# Qwiic_MP3_Trigger.net
KiCad netlist of a schematic drawn in EAGLE
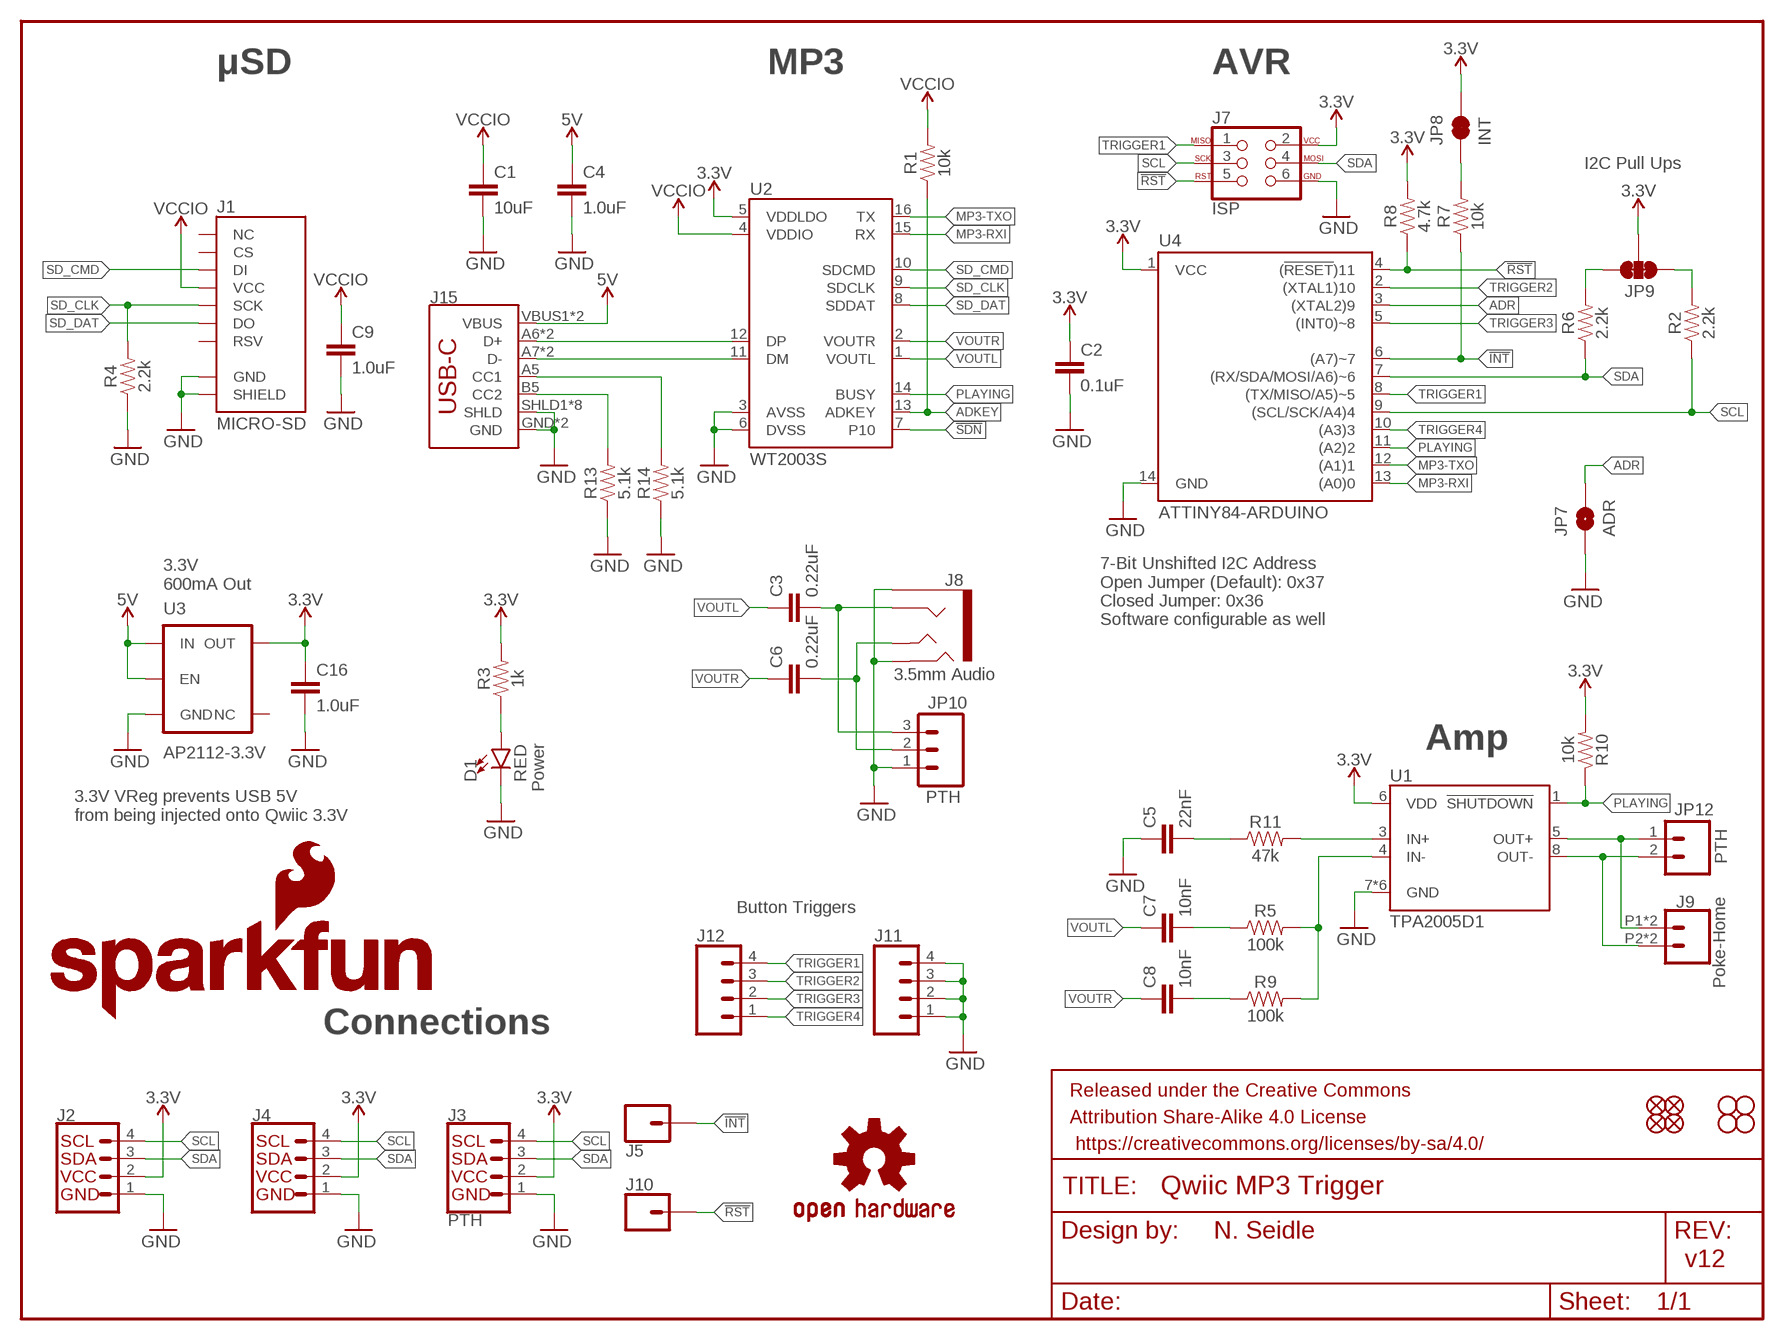
[diagram p0: schematic, sheet 1]

(export (version "E")
  (design (tool "Eeschema 10.0.6"))
  (components
    (comp (ref "C1")
      (value "10uF")
      (footprint "eagle-import:0603")
      (libsource (lib "eagle-import") (part "10UF-0603-6.3V-20%"))
    )
    (comp (ref "C2")
      (value "0.1uF")
      (footprint "eagle-import:0603")
      (libsource (lib "eagle-import") (part "0.1UF-0603-25V-(+80/-20%)"))
    )
    (comp (ref "C3")
      (value "0.22uF")
      (footprint "eagle-import:0603")
      (libsource (lib "eagle-import") (part "0.22UF-0603-25V-10%"))
    )
    (comp (ref "C4")
      (value "1.0uF")
      (footprint "eagle-import:0603")
      (libsource (lib "eagle-import") (part "1.0UF-0603-16V-10%"))
    )
    (comp (ref "C5")
      (value "22nF")
      (footprint "eagle-import:0603")
      (libsource (lib "eagle-import") (part "22NF/22,000PF-0603-50V-10%"))
    )
    (comp (ref "C6")
      (value "0.22uF")
      (footprint "eagle-import:0603")
      (libsource (lib "eagle-import") (part "0.22UF-0603-25V-10%"))
    )
    (comp (ref "C7")
      (value "10nF")
      (footprint "eagle-import:0603")
      (libsource (lib "eagle-import") (part "10NF-0603-50V-10%"))
    )
    (comp (ref "C8")
      (value "10nF")
      (footprint "eagle-import:0603")
      (libsource (lib "eagle-import") (part "10NF-0603-50V-10%"))
    )
    (comp (ref "C9")
      (value "1.0uF")
      (footprint "eagle-import:0603")
      (libsource (lib "eagle-import") (part "1.0UF-0603-16V-10%"))
    )
    (comp (ref "C16")
      (value "1.0uF")
      (footprint "eagle-import:0603")
      (libsource (lib "eagle-import") (part "1.0UF-0603-16V-10%"))
    )
    (comp (ref "D1")
      (value "RED")
      (footprint "eagle-import:LED-0603")
      (libsource (lib "eagle-import") (part "LED-RED0603"))
    )
    (comp (ref "FRAME1")
      (value "FRAME-LETTER")
      (footprint "eagle-import:CREATIVE_COMMONS")
      (libsource (lib "eagle-import") (part "FRAME-LETTER"))
    )
    (comp (ref "J1")
      (value "MICRO-SD")
      (footprint "eagle-import:MICRO-SD-SOCKET")
      (libsource (lib "eagle-import") (part "MICRO-SD_CARD_SOCKETPUSH-PUSH"))
    )
    (comp (ref "J2")
      (value "QWIIC_CONNECTORJS-1MM")
      (footprint "eagle-import:1X04_1MM_RA")
      (libsource (lib "eagle-import") (part "QWIIC_CONNECTORJS-1MM"))
    )
    (comp (ref "J3")
      (value "PTH")
      (footprint "eagle-import:1X04_NO_SILK")
      (libsource (lib "eagle-import") (part "I2C_STANDARD_NO_SILK"))
    )
    (comp (ref "J4")
      (value "QWIIC_CONNECTORJS-1MM")
      (footprint "eagle-import:1X04_1MM_RA")
      (libsource (lib "eagle-import") (part "QWIIC_CONNECTORJS-1MM"))
    )
    (comp (ref "J5")
      (value "CONN_01PTH_NO_SILK_YES_STOP")
      (footprint "eagle-import:1X01_NO_SILK")
      (libsource (lib "eagle-import") (part "CONN_01PTH_NO_SILK_YES_STOP"))
    )
    (comp (ref "J7")
      (value "ISP")
      (footprint "eagle-import:2X3_TEST_POINTS")
      (libsource (lib "eagle-import") (part "AVR_SPI_PROG_3X2TESTPOINTS"))
    )
    (comp (ref "J8")
      (value "3.5mm Audio")
      (footprint "eagle-import:AUDIO_JACK_3.5MM_TRRS_SMD_RA")
      (libsource (lib "eagle-import") (part "AUDIO_JACK_TRRSSMD_RA"))
    )
    (comp (ref "J9")
      (value "Poke-Home")
      (footprint "eagle-import:1X02_POKEHOME")
      (libsource (lib "eagle-import") (part "CONN_02SMALL_POKEHOME"))
    )
    (comp (ref "J10")
      (value "CONN_01PTH_NO_SILK_YES_STOP")
      (footprint "eagle-import:1X01_NO_SILK")
      (libsource (lib "eagle-import") (part "CONN_01PTH_NO_SILK_YES_STOP"))
    )
    (comp (ref "J11")
      (value "CONN_041X04_NO_SILK")
      (footprint "eagle-import:1X04_NO_SILK")
      (libsource (lib "eagle-import") (part "CONN_041X04_NO_SILK"))
    )
    (comp (ref "J12")
      (value "CONN_041X04_NO_SILK")
      (footprint "eagle-import:1X04_NO_SILK")
      (libsource (lib "eagle-import") (part "CONN_041X04_NO_SILK"))
    )
    (comp (ref "J15")
      (value "USB_C16PIN")
      (footprint "eagle-import:USB-C-16P")
      (libsource (lib "eagle-import") (part "USB_C16PIN"))
    )
    (comp (ref "JP1")
      (value "FIDUCIALUFIDUCIAL")
      (footprint "eagle-import:MICRO-FIDUCIAL")
      (libsource (lib "eagle-import") (part "FIDUCIALUFIDUCIAL"))
    )
    (comp (ref "JP2")
      (value "FIDUCIALUFIDUCIAL")
      (footprint "eagle-import:MICRO-FIDUCIAL")
      (libsource (lib "eagle-import") (part "FIDUCIALUFIDUCIAL"))
    )
    (comp (ref "JP3")
      (value "STAND-OFF")
      (footprint "eagle-import:STAND-OFF")
      (libsource (lib "eagle-import") (part "STAND-OFF"))
    )
    (comp (ref "JP4")
      (value "STAND-OFF")
      (footprint "eagle-import:STAND-OFF")
      (libsource (lib "eagle-import") (part "STAND-OFF"))
    )
    (comp (ref "JP5")
      (value "FIDUCIALUFIDUCIAL")
      (footprint "eagle-import:MICRO-FIDUCIAL")
      (libsource (lib "eagle-import") (part "FIDUCIALUFIDUCIAL"))
    )
    (comp (ref "JP6")
      (value "FIDUCIALUFIDUCIAL")
      (footprint "eagle-import:MICRO-FIDUCIAL")
      (libsource (lib "eagle-import") (part "FIDUCIALUFIDUCIAL"))
    )
    (comp (ref "JP7")
      (value "ADR")
      (footprint "eagle-import:SMT-JUMPER_2_NO_SILK")
      (libsource (lib "eagle-import") (part "JUMPER-SMT_2_NO_SILK"))
    )
    (comp (ref "JP8")
      (value "INT")
      (footprint "eagle-import:SMT-JUMPER_2_NC_TRACE_SILK")
      (libsource (lib "eagle-import") (part "JUMPER-SMT_2_NC_TRACE_SILK"))
    )
    (comp (ref "JP9")
      (value "JUMPER-SMT_3_2-NC_TRACE_SILK")
      (footprint "eagle-import:SMT-JUMPER_3_2-NC_TRACE_SILK")
      (libsource (lib "eagle-import") (part "JUMPER-SMT_3_2-NC_TRACE_SILK"))
    )
    (comp (ref "JP10")
      (value "PTH")
      (footprint "eagle-import:1X03_NO_SILK")
      (libsource (lib "eagle-import") (part "CONN_031X03_NO_SILK"))
    )
    (comp (ref "JP11")
      (value "STAND-OFF")
      (footprint "eagle-import:STAND-OFF")
      (libsource (lib "eagle-import") (part "STAND-OFF"))
    )
    (comp (ref "JP12")
      (value "PTH")
      (footprint "eagle-import:1X02_NO_SILK")
      (libsource (lib "eagle-import") (part "CONN_021X02_NO_SILK"))
    )
    (comp (ref "JP13")
      (value "STAND-OFF")
      (footprint "eagle-import:STAND-OFF")
      (libsource (lib "eagle-import") (part "STAND-OFF"))
    )
    (comp (ref "LOGO1")
      (value "OSHW-LOGOMINI")
      (footprint "eagle-import:OSHW-LOGO-MINI")
      (libsource (lib "eagle-import") (part "OSHW-LOGOMINI"))
    )
    (comp (ref "LOGO2")
      (value "SFE_LOGO_NAME.1_INCH")
      (footprint "eagle-import:SFE_LOGO_NAME_.1")
      (libsource (lib "eagle-import") (part "SFE_LOGO_NAME.1_INCH"))
    )
    (comp (ref "LOGO3")
      (value "SFE_LOGO_NAME_FLAME.1_INCH")
      (footprint "eagle-import:SFE_LOGO_NAME_FLAME_.1")
      (libsource (lib "eagle-import") (part "SFE_LOGO_NAME_FLAME.1_INCH"))
    )
    (comp (ref "R1")
      (value "10k")
      (footprint "eagle-import:0603")
      (libsource (lib "eagle-import") (part "10KOHM-0603-1/10W-1%"))
    )
    (comp (ref "R2")
      (value "2.2k")
      (footprint "eagle-import:0603")
      (libsource (lib "eagle-import") (part "2.2KOHM-0603-1/10W-1%"))
    )
    (comp (ref "R3")
      (value "1k")
      (footprint "eagle-import:0603")
      (libsource (lib "eagle-import") (part "1KOHM-0603-1/10W-1%"))
    )
    (comp (ref "R4")
      (value "2.2k")
      (footprint "eagle-import:0603")
      (libsource (lib "eagle-import") (part "2.2KOHM-0603-1/10W-1%"))
    )
    (comp (ref "R5")
      (value "100k")
      (footprint "eagle-import:0603")
      (libsource (lib "eagle-import") (part "100KOHM-0603-1/10W-1%"))
    )
    (comp (ref "R6")
      (value "2.2k")
      (footprint "eagle-import:0603")
      (libsource (lib "eagle-import") (part "2.2KOHM-0603-1/10W-1%"))
    )
    (comp (ref "R7")
      (value "10k")
      (footprint "eagle-import:0603")
      (libsource (lib "eagle-import") (part "10KOHM-0603-1/10W-1%"))
    )
    (comp (ref "R8")
      (value "4.7k")
      (footprint "eagle-import:0603")
      (libsource (lib "eagle-import") (part "4.7KOHM-0603-1/10W-1%"))
    )
    (comp (ref "R9")
      (value "100k")
      (footprint "eagle-import:0603")
      (libsource (lib "eagle-import") (part "100KOHM-0603-1/10W-1%"))
    )
    (comp (ref "R10")
      (value "10k")
      (footprint "eagle-import:0603")
      (libsource (lib "eagle-import") (part "10KOHM-0603-1/10W-1%"))
    )
    (comp (ref "R11")
      (value "47k")
      (footprint "eagle-import:0603")
      (libsource (lib "eagle-import") (part "47KOHM-0603-1/10W-1%"))
    )
    (comp (ref "R13")
      (value "5.1k")
      (footprint "eagle-import:0603")
      (libsource (lib "eagle-import") (part "5.1KOHM5.1KOHM-0603-1/10W-1%"))
    )
    (comp (ref "R14")
      (value "5.1k")
      (footprint "eagle-import:0603")
      (libsource (lib "eagle-import") (part "5.1KOHM5.1KOHM-0603-1/10W-1%"))
    )
    (comp (ref "U1")
      (value "TPA2005D1")
      (footprint "eagle-import:QFN-8_PAD")
      (libsource (lib "eagle-import") (part "TPA2005D1DRB"))
    )
    (comp (ref "U2")
      (value "WT2003S")
      (footprint "eagle-import:SO16")
      (libsource (lib "eagle-import") (part "WT2003S"))
    )
    (comp (ref "U3")
      (value "AP2112-3.3V")
      (footprint "eagle-import:SOT23-5")
      (libsource (lib "eagle-import") (part "V_REG_AP2112K-3.3V"))
    )
    (comp (ref "U4")
      (value "ATTINY84-ARDUINO")
      (footprint "eagle-import:SO14")
      (libsource (lib "eagle-import") (part "ATTINY84-ARDUINO"))
    )
  )
  (nets
    (net (code "1") (name "/~{INT}") (class "Default")
      (node (ref "J5") (pin "1") (pinfunction "1_1") (pintype "passive"))
      (node (ref "R7") (pin "1") (pinfunction "1_1") (pintype "passive"))
      (node (ref "U4") (pin "6") (pinfunction "(A7)~{7}_6") (pintype "bidirectional"))
    )
    (net (code "2") (name "/~{RST}") (class "Default")
      (node (ref "J10") (pin "1") (pinfunction "1_1") (pintype "passive"))
      (node (ref "J7") (pin "5") (pinfunction "5_5") (pintype "passive"))
      (node (ref "R8") (pin "1") (pinfunction "1_1") (pintype "passive"))
      (node (ref "U4") (pin "4") (pinfunction "(~{RESET})11_4") (pintype "bidirectional"))
    )
    (net (code "3") (name "/~{SDN}") (class "Default")
      (node (ref "U2") (pin "7") (pinfunction "P10_7") (pintype "bidirectional"))
    )
    (net (code "4") (name "3.3V") (class "Default")
      (node (ref "C16") (pin "1") (pinfunction "1_1") (pintype "passive"))
      (node (ref "C2") (pin "1") (pinfunction "1_1") (pintype "passive"))
      (node (ref "J2") (pin "2") (pinfunction "2_2") (pintype "power_in"))
      (node (ref "J3") (pin "2") (pinfunction "VCC_2") (pintype "power_in"))
      (node (ref "J4") (pin "2") (pinfunction "2_2") (pintype "power_in"))
      (node (ref "J7") (pin "2") (pinfunction "2_2") (pintype "passive"))
      (node (ref "JP8") (pin "2") (pinfunction "2_2") (pintype "passive"))
      (node (ref "JP9") (pin "2") (pinfunction "2_2") (pintype "passive"))
      (node (ref "R10") (pin "2") (pinfunction "2_2") (pintype "passive"))
      (node (ref "R3") (pin "2") (pinfunction "2_2") (pintype "passive"))
      (node (ref "R8") (pin "2") (pinfunction "2_2") (pintype "passive"))
      (node (ref "U1") (pin "6") (pinfunction "VDD_6") (pintype "power_in"))
      (node (ref "U2") (pin "5") (pinfunction "VDDLDO_5") (pintype "bidirectional"))
      (node (ref "U3") (pin "5") (pinfunction "OUT_5") (pintype "passive"))
      (node (ref "U4") (pin "1") (pinfunction "VCC_1") (pintype "bidirectional"))
    )
    (net (code "5") (name "5V") (class "Default")
      (node (ref "C4") (pin "1") (pinfunction "1_1") (pintype "passive"))
      (node (ref "J15") (pin "VBUS1") (pinfunction "VBUS_VBUS1") (pintype "bidirectional"))
      (node (ref "J15") (pin "VBUS2") (pinfunction "VBUS_VBUS2") (pintype "bidirectional"))
      (node (ref "U3") (pin "1") (pinfunction "IN_1") (pintype "input"))
      (node (ref "U3") (pin "3") (pinfunction "EN_3") (pintype "input"))
    )
    (net (code "6") (name "ADKEY") (class "Default")
      (node (ref "R1") (pin "1") (pinfunction "1_1") (pintype "passive"))
      (node (ref "U2") (pin "13") (pinfunction "ADKEY_13") (pintype "bidirectional"))
    )
    (net (code "7") (name "ADR") (class "Default")
      (node (ref "JP7") (pin "2") (pinfunction "2_2") (pintype "passive"))
      (node (ref "U4") (pin "3") (pinfunction "(XTAL2)9_3") (pintype "bidirectional"))
    )
    (net (code "8") (name "GND") (class "Default")
      (node (ref "C1") (pin "2") (pinfunction "2_2") (pintype "passive"))
      (node (ref "C16") (pin "2") (pinfunction "2_2") (pintype "passive"))
      (node (ref "C2") (pin "2") (pinfunction "2_2") (pintype "passive"))
      (node (ref "C4") (pin "2") (pinfunction "2_2") (pintype "passive"))
      (node (ref "C5") (pin "1") (pinfunction "1_1") (pintype "passive"))
      (node (ref "C9") (pin "2") (pinfunction "2_2") (pintype "passive"))
      (node (ref "D1") (pin "C") (pinfunction "C_C") (pintype "passive"))
      (node (ref "J1") (pin "CD1") (pinfunction "SHIELD_CD1") (pintype "bidirectional"))
      (node (ref "J1") (pin "GND") (pinfunction "GND_GND") (pintype "bidirectional"))
      (node (ref "J11") (pin "1") (pinfunction "1_1") (pintype "passive"))
      (node (ref "J11") (pin "2") (pinfunction "2_2") (pintype "passive"))
      (node (ref "J11") (pin "3") (pinfunction "3_3") (pintype "passive"))
      (node (ref "J11") (pin "4") (pinfunction "4_4") (pintype "passive"))
      (node (ref "J15") (pin "GND") (pinfunction "GND_GND") (pintype "bidirectional"))
      (node (ref "J15") (pin "GND2") (pinfunction "GND_GND2") (pintype "bidirectional"))
      (node (ref "J15") (pin "SHLD1") (pinfunction "SHLD_SHLD1") (pintype "bidirectional"))
      (node (ref "J15") (pin "SHLD2") (pinfunction "SHLD_SHLD2") (pintype "bidirectional"))
      (node (ref "J15") (pin "SHLD3") (pinfunction "SHLD_SHLD3") (pintype "bidirectional"))
      (node (ref "J15") (pin "SHLD4") (pinfunction "SHLD_SHLD4") (pintype "bidirectional"))
      (node (ref "J15") (pin "SHLD5") (pinfunction "SHLD_SHLD5") (pintype "bidirectional"))
      (node (ref "J15") (pin "SHLD6") (pinfunction "SHLD_SHLD6") (pintype "bidirectional"))
      (node (ref "J15") (pin "SHLD7") (pinfunction "SHLD_SHLD7") (pintype "bidirectional"))
      (node (ref "J15") (pin "SHLD8") (pinfunction "SHLD_SHLD8") (pintype "bidirectional"))
      (node (ref "J2") (pin "1") (pinfunction "1_1") (pintype "power_in"))
      (node (ref "J3") (pin "1") (pinfunction "GND_1") (pintype "power_in"))
      (node (ref "J4") (pin "1") (pinfunction "1_1") (pintype "power_in"))
      (node (ref "J7") (pin "6") (pinfunction "6_6") (pintype "passive"))
      (node (ref "J8") (pin "EARTH") (pinfunction "EARTH_EARTH") (pintype "bidirectional"))
      (node (ref "J8") (pin "RING2") (pinfunction "RING2_RING2") (pintype "bidirectional"))
      (node (ref "JP10") (pin "1") (pinfunction "1_1") (pintype "passive"))
      (node (ref "JP7") (pin "1") (pinfunction "1_1") (pintype "passive"))
      (node (ref "R13") (pin "1") (pinfunction "1_1") (pintype "passive"))
      (node (ref "R14") (pin "1") (pinfunction "1_1") (pintype "passive"))
      (node (ref "R4") (pin "1") (pinfunction "1_1") (pintype "passive"))
      (node (ref "U1") (pin "10") (pinfunction "GND_10") (pintype "power_in"))
      (node (ref "U1") (pin "11") (pinfunction "GND_11") (pintype "power_in"))
      (node (ref "U1") (pin "12") (pinfunction "GND_12") (pintype "power_in"))
      (node (ref "U1") (pin "13") (pinfunction "GND_13") (pintype "power_in"))
      (node (ref "U1") (pin "7") (pinfunction "GND_7") (pintype "power_in"))
      (node (ref "U1") (pin "9") (pinfunction "GND_9") (pintype "power_in"))
      (node (ref "U2") (pin "3") (pinfunction "AVSS_3") (pintype "bidirectional"))
      (node (ref "U2") (pin "6") (pinfunction "DVSS_6") (pintype "bidirectional"))
      (node (ref "U3") (pin "2") (pinfunction "GND_2") (pintype "input"))
      (node (ref "U4") (pin "14") (pinfunction "GND_14") (pintype "bidirectional"))
    )
    (net (code "9") (name "MP3-RXI") (class "Default")
      (node (ref "U2") (pin "15") (pinfunction "RX_15") (pintype "bidirectional"))
      (node (ref "U4") (pin "13") (pinfunction "(A0)0_13") (pintype "bidirectional"))
    )
    (net (code "10") (name "MP3-TXO") (class "Default")
      (node (ref "U2") (pin "16") (pinfunction "TX_16") (pintype "bidirectional"))
      (node (ref "U4") (pin "12") (pinfunction "(A1)1_12") (pintype "bidirectional"))
    )
    (net (code "11") (name "Net-(C3-Pad2)") (class "Default")
      (node (ref "C3") (pin "2") (pinfunction "2_2") (pintype "passive"))
      (node (ref "J8") (pin "RING1") (pinfunction "RING1_RING1") (pintype "bidirectional"))
      (node (ref "JP10") (pin "3") (pinfunction "3_3") (pintype "passive"))
    )
    (net (code "12") (name "Net-(C5-Pad2)") (class "Default")
      (node (ref "C5") (pin "2") (pinfunction "2_2") (pintype "passive"))
      (node (ref "R11") (pin "1") (pinfunction "1_1") (pintype "passive"))
    )
    (net (code "13") (name "Net-(C6-Pad2)") (class "Default")
      (node (ref "C6") (pin "2") (pinfunction "2_2") (pintype "passive"))
      (node (ref "J8") (pin "TIP") (pinfunction "TIP_TIP") (pintype "bidirectional"))
      (node (ref "JP10") (pin "2") (pinfunction "2_2") (pintype "passive"))
    )
    (net (code "14") (name "Net-(C7-Pad2)") (class "Default")
      (node (ref "C7") (pin "2") (pinfunction "2_2") (pintype "passive"))
      (node (ref "R5") (pin "1") (pinfunction "1_1") (pintype "passive"))
    )
    (net (code "15") (name "Net-(C8-Pad2)") (class "Default")
      (node (ref "C8") (pin "2") (pinfunction "2_2") (pintype "passive"))
      (node (ref "R9") (pin "1") (pinfunction "1_1") (pintype "passive"))
    )
    (net (code "16") (name "Net-(D1-PadA)") (class "Default")
      (node (ref "D1") (pin "A") (pinfunction "A_A") (pintype "passive"))
      (node (ref "R3") (pin "1") (pinfunction "1_1") (pintype "passive"))
    )
    (net (code "17") (name "Net-(J15-CC1)") (class "Default")
      (node (ref "J15") (pin "A5") (pinfunction "CC1_A5") (pintype "bidirectional"))
      (node (ref "R14") (pin "2") (pinfunction "2_2") (pintype "passive"))
    )
    (net (code "18") (name "Net-(J15-CC2)") (class "Default")
      (node (ref "J15") (pin "B5") (pinfunction "CC2_B5") (pintype "bidirectional"))
      (node (ref "R13") (pin "2") (pinfunction "2_2") (pintype "passive"))
    )
    (net (code "19") (name "Net-(JP8-Pad1)") (class "Default")
      (node (ref "JP8") (pin "1") (pinfunction "1_1") (pintype "passive"))
      (node (ref "R7") (pin "2") (pinfunction "2_2") (pintype "passive"))
    )
    (net (code "20") (name "Net-(JP9-Pad1)") (class "Default")
      (node (ref "JP9") (pin "1") (pinfunction "1_1") (pintype "passive"))
      (node (ref "R2") (pin "2") (pinfunction "2_2") (pintype "passive"))
    )
    (net (code "21") (name "Net-(JP9-Pad3)") (class "Default")
      (node (ref "JP9") (pin "3") (pinfunction "3_3") (pintype "passive"))
      (node (ref "R6") (pin "2") (pinfunction "2_2") (pintype "passive"))
    )
    (net (code "22") (name "Net-(U1-IN+)") (class "Default")
      (node (ref "R11") (pin "2") (pinfunction "2_2") (pintype "passive"))
      (node (ref "U1") (pin "3") (pinfunction "IN+_3") (pintype "bidirectional"))
    )
    (net (code "23") (name "Net-(U1-IN-)") (class "Default")
      (node (ref "R5") (pin "2") (pinfunction "2_2") (pintype "passive"))
      (node (ref "R9") (pin "2") (pinfunction "2_2") (pintype "passive"))
      (node (ref "U1") (pin "4") (pinfunction "IN-_4") (pintype "bidirectional"))
    )
    (net (code "24") (name "Net-(U1-OUT+)") (class "Default")
      (node (ref "J9") (pin "P1") (pinfunction "1_P1") (pintype "passive"))
      (node (ref "J9") (pin "P3") (pinfunction "1_P3") (pintype "passive"))
      (node (ref "JP12") (pin "1") (pinfunction "1_1") (pintype "passive"))
      (node (ref "U1") (pin "5") (pinfunction "OUT+_5") (pintype "bidirectional"))
    )
    (net (code "25") (name "Net-(U1-OUT-)") (class "Default")
      (node (ref "J9") (pin "P2") (pinfunction "2_P2") (pintype "passive"))
      (node (ref "J9") (pin "P4") (pinfunction "2_P4") (pintype "passive"))
      (node (ref "JP12") (pin "2") (pinfunction "2_2") (pintype "passive"))
      (node (ref "U1") (pin "8") (pinfunction "OUT-_8") (pintype "bidirectional"))
    )
    (net (code "26") (name "Net-(U2-DM)") (class "Default")
      (node (ref "J15") (pin "A7") (pinfunction "D-_A7") (pintype "bidirectional"))
      (node (ref "J15") (pin "B7") (pinfunction "D-_B7") (pintype "bidirectional"))
      (node (ref "U2") (pin "11") (pinfunction "DM_11") (pintype "bidirectional"))
    )
    (net (code "27") (name "Net-(U2-DP)") (class "Default")
      (node (ref "J15") (pin "A6") (pinfunction "D+_A6") (pintype "bidirectional"))
      (node (ref "J15") (pin "B6") (pinfunction "D+_B6") (pintype "bidirectional"))
      (node (ref "U2") (pin "12") (pinfunction "DP_12") (pintype "bidirectional"))
    )
    (net (code "28") (name "PLAYING") (class "Default")
      (node (ref "R10") (pin "1") (pinfunction "1_1") (pintype "passive"))
      (node (ref "U1") (pin "1") (pinfunction "~{SHUTDOWN}_1") (pintype "input"))
      (node (ref "U2") (pin "14") (pinfunction "BUSY_14") (pintype "bidirectional"))
      (node (ref "U4") (pin "11") (pinfunction "(A2)2_11") (pintype "bidirectional"))
    )
    (net (code "29") (name "SCL") (class "Default")
      (node (ref "J2") (pin "4") (pinfunction "4_4") (pintype "passive"))
      (node (ref "J3") (pin "4") (pinfunction "SCL_4") (pintype "passive"))
      (node (ref "J4") (pin "4") (pinfunction "4_4") (pintype "passive"))
      (node (ref "J7") (pin "3") (pinfunction "3_3") (pintype "passive"))
      (node (ref "R2") (pin "1") (pinfunction "1_1") (pintype "passive"))
      (node (ref "U4") (pin "9") (pinfunction "(SCL/SCK/A4)4_9") (pintype "bidirectional"))
    )
    (net (code "30") (name "SDA") (class "Default")
      (node (ref "J2") (pin "3") (pinfunction "3_3") (pintype "passive"))
      (node (ref "J3") (pin "3") (pinfunction "SDA_3") (pintype "passive"))
      (node (ref "J4") (pin "3") (pinfunction "3_3") (pintype "passive"))
      (node (ref "J7") (pin "4") (pinfunction "4_4") (pintype "passive"))
      (node (ref "R6") (pin "1") (pinfunction "1_1") (pintype "passive"))
      (node (ref "U4") (pin "7") (pinfunction "(RX/SDA/MOSI/A6)~{6}_7") (pintype "bidirectional"))
    )
    (net (code "31") (name "SD_CLK") (class "Default")
      (node (ref "J1") (pin "SCLK") (pinfunction "SCK_SCLK") (pintype "bidirectional"))
      (node (ref "R4") (pin "2") (pinfunction "2_2") (pintype "passive"))
      (node (ref "U2") (pin "9") (pinfunction "SDCLK_9") (pintype "bidirectional"))
    )
    (net (code "32") (name "SD_CMD") (class "Default")
      (node (ref "J1") (pin "DI") (pinfunction "DI_DI") (pintype "bidirectional"))
      (node (ref "U2") (pin "10") (pinfunction "SDCMD_10") (pintype "bidirectional"))
    )
    (net (code "33") (name "SD_DAT") (class "Default")
      (node (ref "J1") (pin "DO") (pinfunction "DO_DO") (pintype "bidirectional"))
      (node (ref "U2") (pin "8") (pinfunction "SDDAT_8") (pintype "bidirectional"))
    )
    (net (code "34") (name "TRIGGER1") (class "Default")
      (node (ref "J12") (pin "4") (pinfunction "4_4") (pintype "passive"))
      (node (ref "J7") (pin "1") (pinfunction "1_1") (pintype "passive"))
      (node (ref "U4") (pin "8") (pinfunction "(TX/MISO/A5)~{5}_8") (pintype "bidirectional"))
    )
    (net (code "35") (name "TRIGGER2") (class "Default")
      (node (ref "J12") (pin "3") (pinfunction "3_3") (pintype "passive"))
      (node (ref "U4") (pin "2") (pinfunction "(XTAL1)10_2") (pintype "bidirectional"))
    )
    (net (code "36") (name "TRIGGER3") (class "Default")
      (node (ref "J12") (pin "2") (pinfunction "2_2") (pintype "passive"))
      (node (ref "U4") (pin "5") (pinfunction "(INT0)~{8}_5") (pintype "bidirectional"))
    )
    (net (code "37") (name "TRIGGER4") (class "Default")
      (node (ref "J12") (pin "1") (pinfunction "1_1") (pintype "passive"))
      (node (ref "U4") (pin "10") (pinfunction "(A3)3_10") (pintype "bidirectional"))
    )
    (net (code "38") (name "VCCIO") (class "Default")
      (node (ref "C1") (pin "1") (pinfunction "1_1") (pintype "passive"))
      (node (ref "C9") (pin "1") (pinfunction "1_1") (pintype "passive"))
      (node (ref "J1") (pin "VCC") (pinfunction "VCC_VCC") (pintype "bidirectional"))
      (node (ref "R1") (pin "2") (pinfunction "2_2") (pintype "passive"))
      (node (ref "U2") (pin "4") (pinfunction "VDDIO_4") (pintype "bidirectional"))
    )
    (net (code "39") (name "VOUTL") (class "Default")
      (node (ref "C3") (pin "1") (pinfunction "1_1") (pintype "passive"))
      (node (ref "C7") (pin "1") (pinfunction "1_1") (pintype "passive"))
      (node (ref "U2") (pin "1") (pinfunction "VOUTL_1") (pintype "bidirectional"))
    )
    (net (code "40") (name "VOUTR") (class "Default")
      (node (ref "C6") (pin "1") (pinfunction "1_1") (pintype "passive"))
      (node (ref "C8") (pin "1") (pinfunction "1_1") (pintype "passive"))
      (node (ref "U2") (pin "2") (pinfunction "VOUTR_2") (pintype "bidirectional"))
    )
    (net (code "41") (name "unconnected-(J1-NC-PadRSV2)") (class "Default")
      (node (ref "J1") (pin "RSV2") (pinfunction "NC_RSV2") (pintype "bidirectional"))
    )
    (net (code "42") (name "unconnected-(J1-PadCS)") (class "Default")
      (node (ref "J1") (pin "CS") (pinfunction "CS_CS") (pintype "bidirectional"))
    )
    (net (code "43") (name "unconnected-(J1-RSV-PadRSV1)") (class "Default")
      (node (ref "J1") (pin "RSV1") (pinfunction "RSV_RSV1") (pintype "bidirectional"))
    )
    (net (code "44") (name "unconnected-(U3-NC-Pad4)") (class "Default")
      (node (ref "U3") (pin "4") (pinfunction "NC_4") (pintype "input"))
    )
  )
)
